# FatButtons.net
KiCad netlist of a schematic drawn in EAGLE
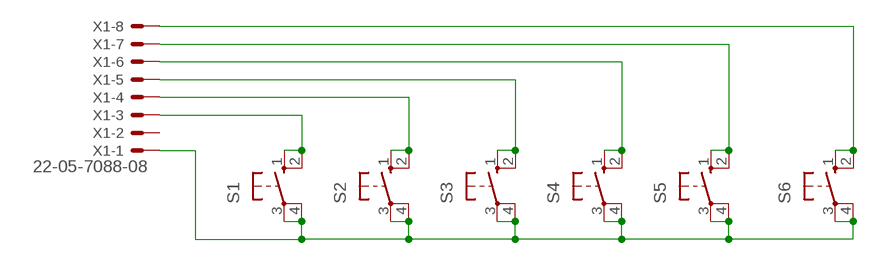
[diagram p0: schematic, sheet 1]

(export (version "E")
  (design (tool "Eeschema 10.0.6"))
  (components
    (comp (ref "S1")
      (value "10-XX")
      (footprint "eagle-import:B3F-10XX")
      (fields (field (name "MPN") "B3F-1000"))
      (libsource (lib "eagle-import") (part "10-XX"))
    )
    (comp (ref "S2")
      (value "10-XX")
      (footprint "eagle-import:B3F-10XX")
      (fields (field (name "MPN") "B3F-1000"))
      (libsource (lib "eagle-import") (part "10-XX"))
    )
    (comp (ref "S3")
      (value "10-XX")
      (footprint "eagle-import:B3F-10XX")
      (fields (field (name "MPN") "B3F-1000"))
      (libsource (lib "eagle-import") (part "10-XX"))
    )
    (comp (ref "S4")
      (value "10-XX")
      (footprint "eagle-import:B3F-10XX")
      (fields (field (name "MPN") "B3F-1000"))
      (libsource (lib "eagle-import") (part "10-XX"))
    )
    (comp (ref "S5")
      (value "10-XX")
      (footprint "eagle-import:B3F-10XX")
      (fields (field (name "MPN") "B3F-1000"))
      (libsource (lib "eagle-import") (part "10-XX"))
    )
    (comp (ref "S6")
      (value "10-XX")
      (footprint "eagle-import:B3F-10XX")
      (fields (field (name "MPN") "B3F-1000"))
      (libsource (lib "eagle-import") (part "10-XX"))
    )
    (comp (ref "X1")
      (value "22-05-7088-08")
      (footprint "eagle-import:7395-08")
      (libsource (lib "eagle-import") (part "22-?-0805-7088"))
    )
  )
  (nets
    (net (code "1") (name "Net-(S1-P)") (class "Default")
      (node (ref "S1") (pin "3") (pinfunction "P_3") (pintype "passive"))
      (node (ref "S1") (pin "4") (pinfunction "P1_4") (pintype "passive"))
      (node (ref "S2") (pin "3") (pinfunction "P_3") (pintype "passive"))
      (node (ref "S2") (pin "4") (pinfunction "P1_4") (pintype "passive"))
      (node (ref "S3") (pin "3") (pinfunction "P_3") (pintype "passive"))
      (node (ref "S3") (pin "4") (pinfunction "P1_4") (pintype "passive"))
      (node (ref "S4") (pin "3") (pinfunction "P_3") (pintype "passive"))
      (node (ref "S4") (pin "4") (pinfunction "P1_4") (pintype "passive"))
      (node (ref "S5") (pin "3") (pinfunction "P_3") (pintype "passive"))
      (node (ref "S5") (pin "4") (pinfunction "P1_4") (pintype "passive"))
      (node (ref "S6") (pin "3") (pinfunction "P_3") (pintype "passive"))
      (node (ref "S6") (pin "4") (pinfunction "P1_4") (pintype "passive"))
      (node (ref "X1") (pin "1") (pinfunction "S_1") (pintype "passive"))
    )
    (net (code "2") (name "Net-(S1-S)") (class "Default")
      (node (ref "S1") (pin "1") (pinfunction "S_1") (pintype "passive"))
      (node (ref "S1") (pin "2") (pinfunction "S1_2") (pintype "passive"))
      (node (ref "X1") (pin "3") (pinfunction "S_3") (pintype "passive"))
    )
    (net (code "3") (name "Net-(S2-S)") (class "Default")
      (node (ref "S2") (pin "1") (pinfunction "S_1") (pintype "passive"))
      (node (ref "S2") (pin "2") (pinfunction "S1_2") (pintype "passive"))
      (node (ref "X1") (pin "4") (pinfunction "S_4") (pintype "passive"))
    )
    (net (code "4") (name "Net-(S3-S)") (class "Default")
      (node (ref "S3") (pin "1") (pinfunction "S_1") (pintype "passive"))
      (node (ref "S3") (pin "2") (pinfunction "S1_2") (pintype "passive"))
      (node (ref "X1") (pin "5") (pinfunction "S_5") (pintype "passive"))
    )
    (net (code "5") (name "Net-(S4-S)") (class "Default")
      (node (ref "S4") (pin "1") (pinfunction "S_1") (pintype "passive"))
      (node (ref "S4") (pin "2") (pinfunction "S1_2") (pintype "passive"))
      (node (ref "X1") (pin "6") (pinfunction "S_6") (pintype "passive"))
    )
    (net (code "6") (name "Net-(S5-S)") (class "Default")
      (node (ref "S5") (pin "1") (pinfunction "S_1") (pintype "passive"))
      (node (ref "S5") (pin "2") (pinfunction "S1_2") (pintype "passive"))
      (node (ref "X1") (pin "7") (pinfunction "S_7") (pintype "passive"))
    )
    (net (code "7") (name "Net-(S6-S)") (class "Default")
      (node (ref "S6") (pin "1") (pinfunction "S_1") (pintype "passive"))
      (node (ref "S6") (pin "2") (pinfunction "S1_2") (pintype "passive"))
      (node (ref "X1") (pin "8") (pinfunction "S_8") (pintype "passive"))
    )
    (net (code "8") (name "unconnected-(X1B-S-Pad2)") (class "Default")
      (node (ref "X1") (pin "2") (pinfunction "S_2") (pintype "passive"))
    )
  )
)
